# tes1.net
KiCad netlist of a schematic drawn in EAGLE
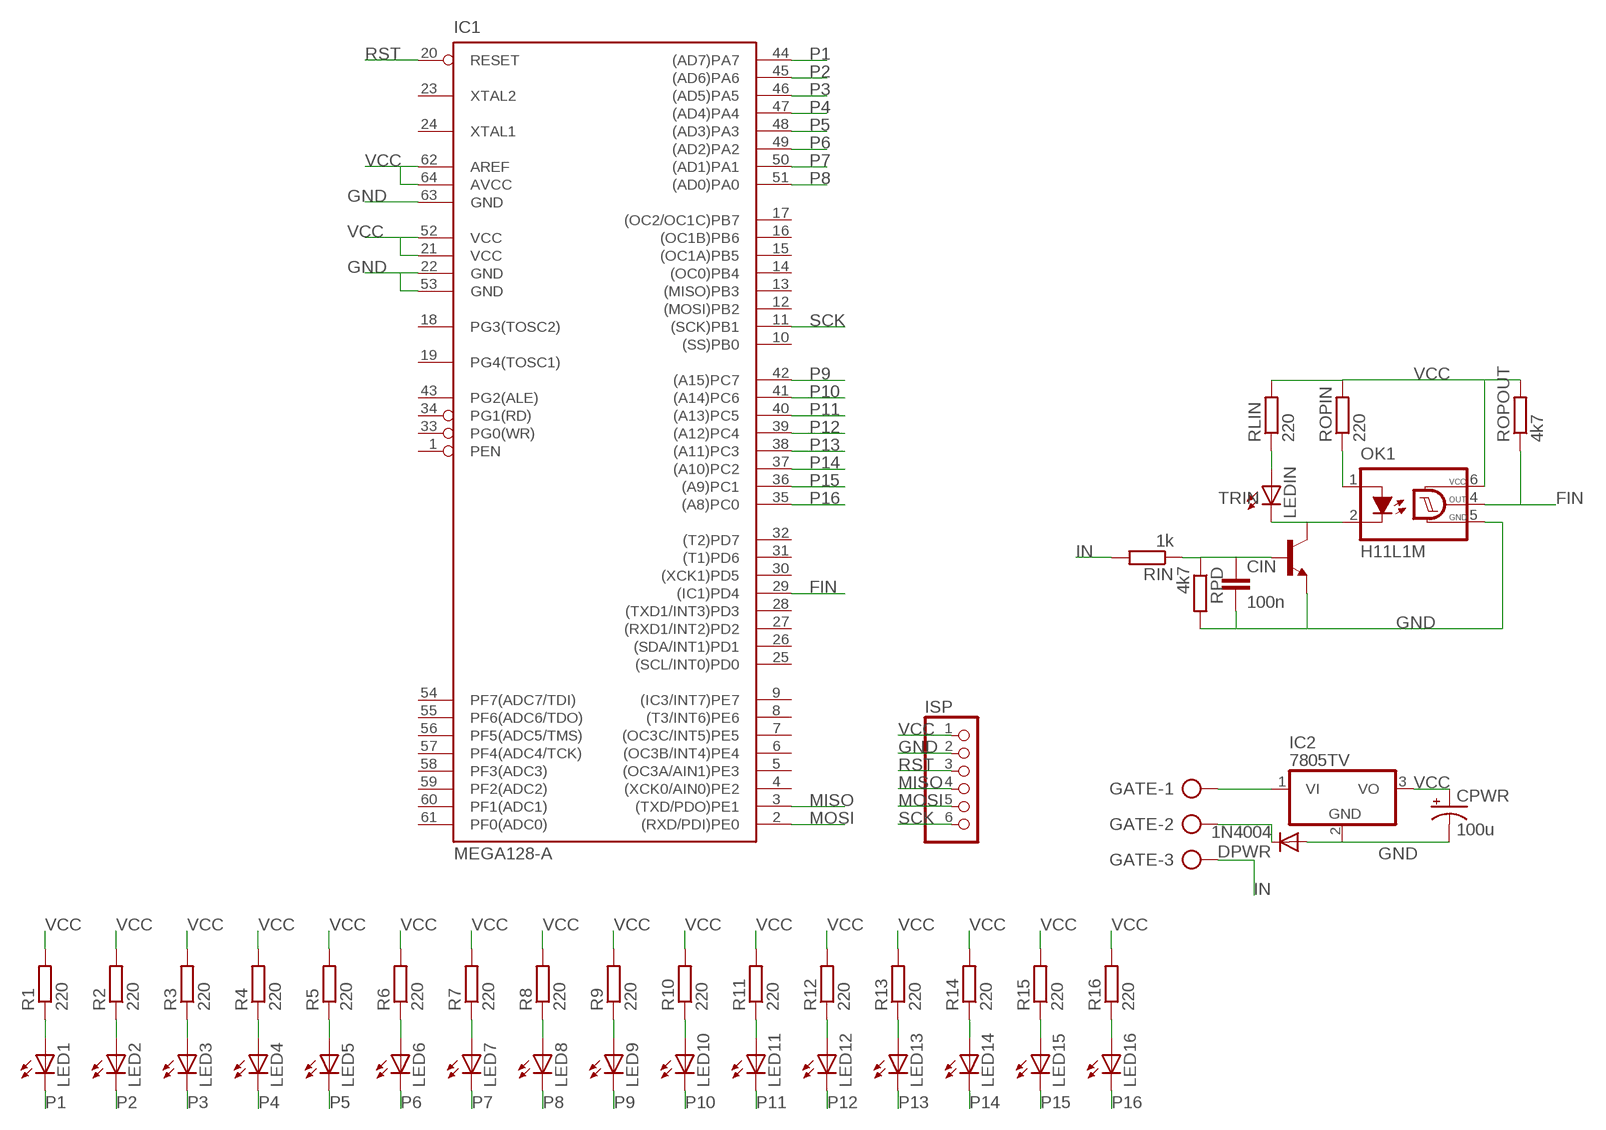
[diagram p0: schematic, sheet 1]

(export (version "E")
  (design (tool "Eeschema 10.0.6"))
  (components
    (comp (ref "CIN")
      (value "100n")
      (footprint "eagle-import:C050-024X044")
      (libsource (lib "eagle-import") (part "C-EU050-024X044"))
    )
    (comp (ref "CPWR")
      (value "100u")
      (footprint "eagle-import:E2-5")
      (libsource (lib "eagle-import") (part "CPOL-USE2-5"))
    )
    (comp (ref "DPWR")
      (value "1N4004")
      (footprint "eagle-import:DO41-10")
      (libsource (lib "eagle-import") (part "1N4004"))
    )
    (comp (ref "GATE")
      (value "AK300/3")
      (footprint "eagle-import:AK300_3")
      (libsource (lib "eagle-import") (part "AK300/3"))
    )
    (comp (ref "IC1")
      (value "MEGA128-A")
      (footprint "eagle-import:TQFP64")
      (fields (field (name "MPN") "ATMEGA128-16AU"))
      (libsource (lib "eagle-import") (part "MEGA128-A"))
    )
    (comp (ref "IC2")
      (value "7805TV")
      (footprint "eagle-import:TO220V")
      (libsource (lib "eagle-import") (part "78TV05"))
    )
    (comp (ref "ISP")
      (value "PINHD-1X6")
      (footprint "eagle-import:1X06")
      (libsource (lib "eagle-import") (part "PINHD-1X6"))
    )
    (comp (ref "LED1")
      (value "LED3MM")
      (footprint "eagle-import:LED3MM")
      (libsource (lib "eagle-import") (part "LED3MM"))
    )
    (comp (ref "LED2")
      (value "LED3MM")
      (footprint "eagle-import:LED3MM")
      (libsource (lib "eagle-import") (part "LED3MM"))
    )
    (comp (ref "LED3")
      (value "LED3MM")
      (footprint "eagle-import:LED3MM")
      (libsource (lib "eagle-import") (part "LED3MM"))
    )
    (comp (ref "LED4")
      (value "LED3MM")
      (footprint "eagle-import:LED3MM")
      (libsource (lib "eagle-import") (part "LED3MM"))
    )
    (comp (ref "LED5")
      (value "LED3MM")
      (footprint "eagle-import:LED3MM")
      (libsource (lib "eagle-import") (part "LED3MM"))
    )
    (comp (ref "LED6")
      (value "LED3MM")
      (footprint "eagle-import:LED3MM")
      (libsource (lib "eagle-import") (part "LED3MM"))
    )
    (comp (ref "LED7")
      (value "LED3MM")
      (footprint "eagle-import:LED3MM")
      (libsource (lib "eagle-import") (part "LED3MM"))
    )
    (comp (ref "LED8")
      (value "LED3MM")
      (footprint "eagle-import:LED3MM")
      (libsource (lib "eagle-import") (part "LED3MM"))
    )
    (comp (ref "LED9")
      (value "LED3MM")
      (footprint "eagle-import:LED3MM")
      (libsource (lib "eagle-import") (part "LED3MM"))
    )
    (comp (ref "LED10")
      (value "LED3MM")
      (footprint "eagle-import:LED3MM")
      (libsource (lib "eagle-import") (part "LED3MM"))
    )
    (comp (ref "LED11")
      (value "LED3MM")
      (footprint "eagle-import:LED3MM")
      (libsource (lib "eagle-import") (part "LED3MM"))
    )
    (comp (ref "LED12")
      (value "LED3MM")
      (footprint "eagle-import:LED3MM")
      (libsource (lib "eagle-import") (part "LED3MM"))
    )
    (comp (ref "LED13")
      (value "LED3MM")
      (footprint "eagle-import:LED3MM")
      (libsource (lib "eagle-import") (part "LED3MM"))
    )
    (comp (ref "LED14")
      (value "LED3MM")
      (footprint "eagle-import:LED3MM")
      (libsource (lib "eagle-import") (part "LED3MM"))
    )
    (comp (ref "LED15")
      (value "LED3MM")
      (footprint "eagle-import:LED3MM")
      (libsource (lib "eagle-import") (part "LED3MM"))
    )
    (comp (ref "LED16")
      (value "LED3MM")
      (footprint "eagle-import:LED3MM")
      (libsource (lib "eagle-import") (part "LED3MM"))
    )
    (comp (ref "LEDIN")
      (value "LED3MM")
      (footprint "eagle-import:LED3MM")
      (libsource (lib "eagle-import") (part "LED3MM"))
    )
    (comp (ref "OK1")
      (value "H11L1M")
      (footprint "eagle-import:DIL06")
      (fields (field (name "MF") "FAIRCHILD SEMICONDUCTOR") (field (name "MPN") "H11L1-M"))
      (libsource (lib "eagle-import") (part "H11LM1"))
    )
    (comp (ref "R1")
      (value "220")
      (footprint "eagle-import:0204_7")
      (libsource (lib "eagle-import") (part "R-EU_0204/7"))
    )
    (comp (ref "R2")
      (value "220")
      (footprint "eagle-import:0204_7")
      (libsource (lib "eagle-import") (part "R-EU_0204/7"))
    )
    (comp (ref "R3")
      (value "220")
      (footprint "eagle-import:0204_7")
      (libsource (lib "eagle-import") (part "R-EU_0204/7"))
    )
    (comp (ref "R4")
      (value "220")
      (footprint "eagle-import:0204_7")
      (libsource (lib "eagle-import") (part "R-EU_0204/7"))
    )
    (comp (ref "R5")
      (value "220")
      (footprint "eagle-import:0204_7")
      (libsource (lib "eagle-import") (part "R-EU_0204/7"))
    )
    (comp (ref "R6")
      (value "220")
      (footprint "eagle-import:0204_7")
      (libsource (lib "eagle-import") (part "R-EU_0204/7"))
    )
    (comp (ref "R7")
      (value "220")
      (footprint "eagle-import:0204_7")
      (libsource (lib "eagle-import") (part "R-EU_0204/7"))
    )
    (comp (ref "R8")
      (value "220")
      (footprint "eagle-import:0204_7")
      (libsource (lib "eagle-import") (part "R-EU_0204/7"))
    )
    (comp (ref "R9")
      (value "220")
      (footprint "eagle-import:0204_7")
      (libsource (lib "eagle-import") (part "R-EU_0204/7"))
    )
    (comp (ref "R10")
      (value "220")
      (footprint "eagle-import:0204_7")
      (libsource (lib "eagle-import") (part "R-EU_0204/7"))
    )
    (comp (ref "R11")
      (value "220")
      (footprint "eagle-import:0204_7")
      (libsource (lib "eagle-import") (part "R-EU_0204/7"))
    )
    (comp (ref "R12")
      (value "220")
      (footprint "eagle-import:0204_7")
      (libsource (lib "eagle-import") (part "R-EU_0204/7"))
    )
    (comp (ref "R13")
      (value "220")
      (footprint "eagle-import:0204_7")
      (libsource (lib "eagle-import") (part "R-EU_0204/7"))
    )
    (comp (ref "R14")
      (value "220")
      (footprint "eagle-import:0204_7")
      (libsource (lib "eagle-import") (part "R-EU_0204/7"))
    )
    (comp (ref "R15")
      (value "220")
      (footprint "eagle-import:0204_7")
      (libsource (lib "eagle-import") (part "R-EU_0204/7"))
    )
    (comp (ref "R16")
      (value "220")
      (footprint "eagle-import:0204_7")
      (libsource (lib "eagle-import") (part "R-EU_0204/7"))
    )
    (comp (ref "RIN")
      (value "1k")
      (footprint "eagle-import:0204_7")
      (libsource (lib "eagle-import") (part "R-EU_0204/7"))
    )
    (comp (ref "RLIN")
      (value "220")
      (footprint "eagle-import:0204_7")
      (libsource (lib "eagle-import") (part "R-EU_0204/7"))
    )
    (comp (ref "ROPIN")
      (value "220")
      (footprint "eagle-import:0204_7")
      (libsource (lib "eagle-import") (part "R-EU_0204/7"))
    )
    (comp (ref "ROPOUT")
      (value "4k7")
      (footprint "eagle-import:0204_7")
      (libsource (lib "eagle-import") (part "R-EU_0204/7"))
    )
    (comp (ref "RPD")
      (value "4k7")
      (footprint "eagle-import:0204_7")
      (libsource (lib "eagle-import") (part "R-EU_0204/7"))
    )
    (comp (ref "TRIN")
      (value "-NPN-TO92-EBC")
      (footprint "eagle-import:TO92-EBC")
      (libsource (lib "eagle-import") (part "-NPN-TO92-EBC"))
    )
  )
  (nets
    (net (code "1") (name "/FIN") (class "Default")
      (node (ref "IC1") (pin "29") (pinfunction "(IC1)PD4_29") (pintype "bidirectional"))
      (node (ref "OK1") (pin "4") (pinfunction "OUT_4") (pintype "output"))
      (node (ref "ROPOUT") (pin "1") (pinfunction "1_1") (pintype "passive"))
    )
    (net (code "2") (name "/GND") (class "Default")
      (node (ref "CIN") (pin "2") (pinfunction "2_2") (pintype "passive"))
      (node (ref "CPWR") (pin "-") (pinfunction "-_-") (pintype "passive"))
      (node (ref "DPWR") (pin "A") (pinfunction "A_A") (pintype "passive"))
      (node (ref "IC1") (pin "22") (pinfunction "GND_22") (pintype "power_in"))
      (node (ref "IC1") (pin "53") (pinfunction "GND_53") (pintype "power_in"))
      (node (ref "IC1") (pin "63") (pinfunction "GND_63") (pintype "power_in"))
      (node (ref "IC2") (pin "2") (pinfunction "GND_2") (pintype "passive"))
      (node (ref "ISP") (pin "2") (pinfunction "2_2") (pintype "passive"))
      (node (ref "OK1") (pin "5") (pinfunction "GND_5") (pintype "power_in"))
      (node (ref "RPD") (pin "2") (pinfunction "2_2") (pintype "passive"))
      (node (ref "TRIN") (pin "E") (pinfunction "E_E") (pintype "passive"))
    )
    (net (code "3") (name "/IN") (class "Default")
      (node (ref "GATE") (pin "3") (pinfunction "KL_3") (pintype "passive"))
      (node (ref "RIN") (pin "2") (pinfunction "2_2") (pintype "passive"))
    )
    (net (code "4") (name "/MISO") (class "Default")
      (node (ref "IC1") (pin "3") (pinfunction "(TXD/PDO)PE1_3") (pintype "bidirectional"))
      (node (ref "ISP") (pin "4") (pinfunction "4_4") (pintype "passive"))
    )
    (net (code "5") (name "/MOSI") (class "Default")
      (node (ref "IC1") (pin "2") (pinfunction "(RXD/PDI)PE0_2") (pintype "bidirectional"))
      (node (ref "ISP") (pin "5") (pinfunction "5_5") (pintype "passive"))
    )
    (net (code "6") (name "/P1") (class "Default")
      (node (ref "IC1") (pin "44") (pinfunction "(AD7)PA7_44") (pintype "bidirectional"))
      (node (ref "LED1") (pin "K") (pinfunction "C_K") (pintype "passive"))
    )
    (net (code "7") (name "/P2") (class "Default")
      (node (ref "IC1") (pin "45") (pinfunction "(AD6)PA6_45") (pintype "bidirectional"))
      (node (ref "LED2") (pin "K") (pinfunction "C_K") (pintype "passive"))
    )
    (net (code "8") (name "/P3") (class "Default")
      (node (ref "IC1") (pin "46") (pinfunction "(AD5)PA5_46") (pintype "bidirectional"))
      (node (ref "LED3") (pin "K") (pinfunction "C_K") (pintype "passive"))
    )
    (net (code "9") (name "/P4") (class "Default")
      (node (ref "IC1") (pin "47") (pinfunction "(AD4)PA4_47") (pintype "bidirectional"))
      (node (ref "LED4") (pin "K") (pinfunction "C_K") (pintype "passive"))
    )
    (net (code "10") (name "/P5") (class "Default")
      (node (ref "IC1") (pin "48") (pinfunction "(AD3)PA3_48") (pintype "bidirectional"))
      (node (ref "LED5") (pin "K") (pinfunction "C_K") (pintype "passive"))
    )
    (net (code "11") (name "/P6") (class "Default")
      (node (ref "IC1") (pin "49") (pinfunction "(AD2)PA2_49") (pintype "bidirectional"))
      (node (ref "LED6") (pin "K") (pinfunction "C_K") (pintype "passive"))
    )
    (net (code "12") (name "/P7") (class "Default")
      (node (ref "IC1") (pin "50") (pinfunction "(AD1)PA1_50") (pintype "bidirectional"))
      (node (ref "LED7") (pin "K") (pinfunction "C_K") (pintype "passive"))
    )
    (net (code "13") (name "/P8") (class "Default")
      (node (ref "IC1") (pin "51") (pinfunction "(AD0)PA0_51") (pintype "bidirectional"))
      (node (ref "LED8") (pin "K") (pinfunction "C_K") (pintype "passive"))
    )
    (net (code "14") (name "/P9") (class "Default")
      (node (ref "IC1") (pin "42") (pinfunction "(A15)PC7_42") (pintype "output"))
      (node (ref "LED9") (pin "K") (pinfunction "C_K") (pintype "passive"))
    )
    (net (code "15") (name "/P10") (class "Default")
      (node (ref "IC1") (pin "41") (pinfunction "(A14)PC6_41") (pintype "output"))
      (node (ref "LED10") (pin "K") (pinfunction "C_K") (pintype "passive"))
    )
    (net (code "16") (name "/P11") (class "Default")
      (node (ref "IC1") (pin "40") (pinfunction "(A13)PC5_40") (pintype "output"))
      (node (ref "LED11") (pin "K") (pinfunction "C_K") (pintype "passive"))
    )
    (net (code "17") (name "/P12") (class "Default")
      (node (ref "IC1") (pin "39") (pinfunction "(A12)PC4_39") (pintype "output"))
      (node (ref "LED12") (pin "K") (pinfunction "C_K") (pintype "passive"))
    )
    (net (code "18") (name "/P13") (class "Default")
      (node (ref "IC1") (pin "38") (pinfunction "(A11)PC3_38") (pintype "output"))
      (node (ref "LED13") (pin "K") (pinfunction "C_K") (pintype "passive"))
    )
    (net (code "19") (name "/P14") (class "Default")
      (node (ref "IC1") (pin "37") (pinfunction "(A10)PC2_37") (pintype "output"))
      (node (ref "LED14") (pin "K") (pinfunction "C_K") (pintype "passive"))
    )
    (net (code "20") (name "/P15") (class "Default")
      (node (ref "IC1") (pin "36") (pinfunction "(A9)PC1_36") (pintype "output"))
      (node (ref "LED15") (pin "K") (pinfunction "C_K") (pintype "passive"))
    )
    (net (code "21") (name "/P16") (class "Default")
      (node (ref "IC1") (pin "35") (pinfunction "(A8)PC0_35") (pintype "output"))
      (node (ref "LED16") (pin "K") (pinfunction "C_K") (pintype "passive"))
    )
    (net (code "22") (name "/RST") (class "Default")
      (node (ref "IC1") (pin "20") (pinfunction "RESET_20") (pintype "input"))
      (node (ref "ISP") (pin "3") (pinfunction "3_3") (pintype "passive"))
    )
    (net (code "23") (name "/SCK") (class "Default")
      (node (ref "IC1") (pin "11") (pinfunction "(SCK)PB1_11") (pintype "bidirectional"))
      (node (ref "ISP") (pin "6") (pinfunction "6_6") (pintype "passive"))
    )
    (net (code "24") (name "/VCC") (class "Default")
      (node (ref "CPWR") (pin "+") (pinfunction "+_+") (pintype "passive"))
      (node (ref "IC1") (pin "21") (pinfunction "VCC_21") (pintype "power_in"))
      (node (ref "IC1") (pin "52") (pinfunction "VCC_52") (pintype "power_in"))
      (node (ref "IC1") (pin "62") (pinfunction "AREF_62") (pintype "passive"))
      (node (ref "IC1") (pin "64") (pinfunction "AVCC_64") (pintype "power_in"))
      (node (ref "IC2") (pin "3") (pinfunction "VO_3") (pintype "passive"))
      (node (ref "ISP") (pin "1") (pinfunction "1_1") (pintype "passive"))
      (node (ref "OK1") (pin "6") (pinfunction "VCC_6") (pintype "power_in"))
      (node (ref "R1") (pin "2") (pinfunction "2_2") (pintype "passive"))
      (node (ref "R10") (pin "2") (pinfunction "2_2") (pintype "passive"))
      (node (ref "R11") (pin "2") (pinfunction "2_2") (pintype "passive"))
      (node (ref "R12") (pin "2") (pinfunction "2_2") (pintype "passive"))
      (node (ref "R13") (pin "2") (pinfunction "2_2") (pintype "passive"))
      (node (ref "R14") (pin "2") (pinfunction "2_2") (pintype "passive"))
      (node (ref "R15") (pin "2") (pinfunction "2_2") (pintype "passive"))
      (node (ref "R16") (pin "2") (pinfunction "2_2") (pintype "passive"))
      (node (ref "R2") (pin "2") (pinfunction "2_2") (pintype "passive"))
      (node (ref "R3") (pin "2") (pinfunction "2_2") (pintype "passive"))
      (node (ref "R4") (pin "2") (pinfunction "2_2") (pintype "passive"))
      (node (ref "R5") (pin "2") (pinfunction "2_2") (pintype "passive"))
      (node (ref "R6") (pin "2") (pinfunction "2_2") (pintype "passive"))
      (node (ref "R7") (pin "2") (pinfunction "2_2") (pintype "passive"))
      (node (ref "R8") (pin "2") (pinfunction "2_2") (pintype "passive"))
      (node (ref "R9") (pin "2") (pinfunction "2_2") (pintype "passive"))
      (node (ref "RLIN") (pin "2") (pinfunction "2_2") (pintype "passive"))
      (node (ref "ROPIN") (pin "2") (pinfunction "2_2") (pintype "passive"))
      (node (ref "ROPOUT") (pin "2") (pinfunction "2_2") (pintype "passive"))
    )
    (net (code "25") (name "Net-(CIN-Pad1)") (class "Default")
      (node (ref "CIN") (pin "1") (pinfunction "1_1") (pintype "passive"))
      (node (ref "RIN") (pin "1") (pinfunction "1_1") (pintype "passive"))
      (node (ref "RPD") (pin "1") (pinfunction "1_1") (pintype "passive"))
      (node (ref "TRIN") (pin "B") (pinfunction "B_B") (pintype "passive"))
    )
    (net (code "26") (name "Net-(GATEA-KL)") (class "Default")
      (node (ref "GATE") (pin "1") (pinfunction "KL_1") (pintype "passive"))
      (node (ref "IC2") (pin "1") (pinfunction "VI_1") (pintype "input"))
    )
    (net (code "27") (name "Net-(GATEB-KL)") (class "Default")
      (node (ref "DPWR") (pin "C") (pinfunction "C_C") (pintype "passive"))
      (node (ref "GATE") (pin "2") (pinfunction "KL_2") (pintype "passive"))
    )
    (net (code "28") (name "Net-(LED1-PadA)") (class "Default")
      (node (ref "LED1") (pin "A") (pinfunction "A_A") (pintype "passive"))
      (node (ref "R1") (pin "1") (pinfunction "1_1") (pintype "passive"))
    )
    (net (code "29") (name "Net-(LED2-PadA)") (class "Default")
      (node (ref "LED2") (pin "A") (pinfunction "A_A") (pintype "passive"))
      (node (ref "R2") (pin "1") (pinfunction "1_1") (pintype "passive"))
    )
    (net (code "30") (name "Net-(LED3-PadA)") (class "Default")
      (node (ref "LED3") (pin "A") (pinfunction "A_A") (pintype "passive"))
      (node (ref "R3") (pin "1") (pinfunction "1_1") (pintype "passive"))
    )
    (net (code "31") (name "Net-(LED4-PadA)") (class "Default")
      (node (ref "LED4") (pin "A") (pinfunction "A_A") (pintype "passive"))
      (node (ref "R4") (pin "1") (pinfunction "1_1") (pintype "passive"))
    )
    (net (code "32") (name "Net-(LED5-PadA)") (class "Default")
      (node (ref "LED5") (pin "A") (pinfunction "A_A") (pintype "passive"))
      (node (ref "R5") (pin "1") (pinfunction "1_1") (pintype "passive"))
    )
    (net (code "33") (name "Net-(LED6-PadA)") (class "Default")
      (node (ref "LED6") (pin "A") (pinfunction "A_A") (pintype "passive"))
      (node (ref "R6") (pin "1") (pinfunction "1_1") (pintype "passive"))
    )
    (net (code "34") (name "Net-(LED7-PadA)") (class "Default")
      (node (ref "LED7") (pin "A") (pinfunction "A_A") (pintype "passive"))
      (node (ref "R7") (pin "1") (pinfunction "1_1") (pintype "passive"))
    )
    (net (code "35") (name "Net-(LED8-PadA)") (class "Default")
      (node (ref "LED8") (pin "A") (pinfunction "A_A") (pintype "passive"))
      (node (ref "R8") (pin "1") (pinfunction "1_1") (pintype "passive"))
    )
    (net (code "36") (name "Net-(LED9-PadA)") (class "Default")
      (node (ref "LED9") (pin "A") (pinfunction "A_A") (pintype "passive"))
      (node (ref "R9") (pin "1") (pinfunction "1_1") (pintype "passive"))
    )
    (net (code "37") (name "Net-(LED10-PadA)") (class "Default")
      (node (ref "LED10") (pin "A") (pinfunction "A_A") (pintype "passive"))
      (node (ref "R10") (pin "1") (pinfunction "1_1") (pintype "passive"))
    )
    (net (code "38") (name "Net-(LED11-PadA)") (class "Default")
      (node (ref "LED11") (pin "A") (pinfunction "A_A") (pintype "passive"))
      (node (ref "R11") (pin "1") (pinfunction "1_1") (pintype "passive"))
    )
    (net (code "39") (name "Net-(LED12-PadA)") (class "Default")
      (node (ref "LED12") (pin "A") (pinfunction "A_A") (pintype "passive"))
      (node (ref "R12") (pin "1") (pinfunction "1_1") (pintype "passive"))
    )
    (net (code "40") (name "Net-(LED13-PadA)") (class "Default")
      (node (ref "LED13") (pin "A") (pinfunction "A_A") (pintype "passive"))
      (node (ref "R13") (pin "1") (pinfunction "1_1") (pintype "passive"))
    )
    (net (code "41") (name "Net-(LED14-PadA)") (class "Default")
      (node (ref "LED14") (pin "A") (pinfunction "A_A") (pintype "passive"))
      (node (ref "R14") (pin "1") (pinfunction "1_1") (pintype "passive"))
    )
    (net (code "42") (name "Net-(LED15-PadA)") (class "Default")
      (node (ref "LED15") (pin "A") (pinfunction "A_A") (pintype "passive"))
      (node (ref "R15") (pin "1") (pinfunction "1_1") (pintype "passive"))
    )
    (net (code "43") (name "Net-(LED16-PadA)") (class "Default")
      (node (ref "LED16") (pin "A") (pinfunction "A_A") (pintype "passive"))
      (node (ref "R16") (pin "1") (pinfunction "1_1") (pintype "passive"))
    )
    (net (code "44") (name "Net-(LEDIN-C)") (class "Default")
      (node (ref "LEDIN") (pin "K") (pinfunction "C_K") (pintype "passive"))
      (node (ref "OK1") (pin "2") (pinfunction "C_2") (pintype "passive"))
      (node (ref "TRIN") (pin "C") (pinfunction "C_C") (pintype "passive"))
    )
    (net (code "45") (name "Net-(LEDIN-PadA)") (class "Default")
      (node (ref "LEDIN") (pin "A") (pinfunction "A_A") (pintype "passive"))
      (node (ref "RLIN") (pin "1") (pinfunction "1_1") (pintype "passive"))
    )
    (net (code "46") (name "Net-(OK1-A)") (class "Default")
      (node (ref "OK1") (pin "1") (pinfunction "A_1") (pintype "passive"))
      (node (ref "ROPIN") (pin "1") (pinfunction "1_1") (pintype "passive"))
    )
    (net (code "47") (name "unconnected-(IC1-(IC3{slash}INT7)PE7-Pad9)") (class "Default")
      (node (ref "IC1") (pin "9") (pinfunction "(IC3/INT7)PE7_9") (pintype "bidirectional"))
    )
    (net (code "48") (name "unconnected-(IC1-(MISO)PB3-Pad13)") (class "Default")
      (node (ref "IC1") (pin "13") (pinfunction "(MISO)PB3_13") (pintype "bidirectional"))
    )
    (net (code "49") (name "unconnected-(IC1-(MOSI)PB2-Pad12)") (class "Default")
      (node (ref "IC1") (pin "12") (pinfunction "(MOSI)PB2_12") (pintype "bidirectional"))
    )
    (net (code "50") (name "unconnected-(IC1-(OC0)PB4-Pad14)") (class "Default")
      (node (ref "IC1") (pin "14") (pinfunction "(OC0)PB4_14") (pintype "bidirectional"))
    )
    (net (code "51") (name "unconnected-(IC1-(OC1A)PB5-Pad15)") (class "Default")
      (node (ref "IC1") (pin "15") (pinfunction "(OC1A)PB5_15") (pintype "bidirectional"))
    )
    (net (code "52") (name "unconnected-(IC1-(OC1B)PB6-Pad16)") (class "Default")
      (node (ref "IC1") (pin "16") (pinfunction "(OC1B)PB6_16") (pintype "bidirectional"))
    )
    (net (code "53") (name "unconnected-(IC1-(OC2{slash}OC1C)PB7-Pad17)") (class "Default")
      (node (ref "IC1") (pin "17") (pinfunction "(OC2/OC1C)PB7_17") (pintype "bidirectional"))
    )
    (net (code "54") (name "unconnected-(IC1-(OC3A{slash}AIN1)PE3-Pad5)") (class "Default")
      (node (ref "IC1") (pin "5") (pinfunction "(OC3A/AIN1)PE3_5") (pintype "bidirectional"))
    )
    (net (code "55") (name "unconnected-(IC1-(OC3B{slash}INT4)PE4-Pad6)") (class "Default")
      (node (ref "IC1") (pin "6") (pinfunction "(OC3B/INT4)PE4_6") (pintype "bidirectional"))
    )
    (net (code "56") (name "unconnected-(IC1-(OC3C{slash}INT5)PE5-Pad7)") (class "Default")
      (node (ref "IC1") (pin "7") (pinfunction "(OC3C/INT5)PE5_7") (pintype "bidirectional"))
    )
    (net (code "57") (name "unconnected-(IC1-(RXD1{slash}INT2)PD2-Pad27)") (class "Default")
      (node (ref "IC1") (pin "27") (pinfunction "(RXD1/INT2)PD2_27") (pintype "bidirectional"))
    )
    (net (code "58") (name "unconnected-(IC1-(SCL{slash}INT0)PD0-Pad25)") (class "Default")
      (node (ref "IC1") (pin "25") (pinfunction "(SCL/INT0)PD0_25") (pintype "bidirectional"))
    )
    (net (code "59") (name "unconnected-(IC1-(SDA{slash}INT1)PD1-Pad26)") (class "Default")
      (node (ref "IC1") (pin "26") (pinfunction "(SDA/INT1)PD1_26") (pintype "bidirectional"))
    )
    (net (code "60") (name "unconnected-(IC1-(SS)PB0-Pad10)") (class "Default")
      (node (ref "IC1") (pin "10") (pinfunction "(SS)PB0_10") (pintype "bidirectional"))
    )
    (net (code "61") (name "unconnected-(IC1-(T1)PD6-Pad31)") (class "Default")
      (node (ref "IC1") (pin "31") (pinfunction "(T1)PD6_31") (pintype "bidirectional"))
    )
    (net (code "62") (name "unconnected-(IC1-(T2)PD7-Pad32)") (class "Default")
      (node (ref "IC1") (pin "32") (pinfunction "(T2)PD7_32") (pintype "bidirectional"))
    )
    (net (code "63") (name "unconnected-(IC1-(T3{slash}INT6)PE6-Pad8)") (class "Default")
      (node (ref "IC1") (pin "8") (pinfunction "(T3/INT6)PE6_8") (pintype "bidirectional"))
    )
    (net (code "64") (name "unconnected-(IC1-(TXD1{slash}INT3)PD3-Pad28)") (class "Default")
      (node (ref "IC1") (pin "28") (pinfunction "(TXD1/INT3)PD3_28") (pintype "bidirectional"))
    )
    (net (code "65") (name "unconnected-(IC1-(XCK0{slash}AIN0)PE2-Pad4)") (class "Default")
      (node (ref "IC1") (pin "4") (pinfunction "(XCK0/AIN0)PE2_4") (pintype "bidirectional"))
    )
    (net (code "66") (name "unconnected-(IC1-(XCK1)PD5-Pad30)") (class "Default")
      (node (ref "IC1") (pin "30") (pinfunction "(XCK1)PD5_30") (pintype "bidirectional"))
    )
    (net (code "67") (name "unconnected-(IC1-PEN-Pad1)") (class "Default")
      (node (ref "IC1") (pin "1") (pinfunction "PEN_1") (pintype "input"))
    )
    (net (code "68") (name "unconnected-(IC1-PF0(ADC0)-Pad61)") (class "Default")
      (node (ref "IC1") (pin "61") (pinfunction "PF0(ADC0)_61") (pintype "input"))
    )
    (net (code "69") (name "unconnected-(IC1-PF1(ADC1)-Pad60)") (class "Default")
      (node (ref "IC1") (pin "60") (pinfunction "PF1(ADC1)_60") (pintype "input"))
    )
    (net (code "70") (name "unconnected-(IC1-PF2(ADC2)-Pad59)") (class "Default")
      (node (ref "IC1") (pin "59") (pinfunction "PF2(ADC2)_59") (pintype "input"))
    )
    (net (code "71") (name "unconnected-(IC1-PF3(ADC3)-Pad58)") (class "Default")
      (node (ref "IC1") (pin "58") (pinfunction "PF3(ADC3)_58") (pintype "input"))
    )
    (net (code "72") (name "unconnected-(IC1-PF4(ADC4{slash}TCK)-Pad57)") (class "Default")
      (node (ref "IC1") (pin "57") (pinfunction "PF4(ADC4/TCK)_57") (pintype "input"))
    )
    (net (code "73") (name "unconnected-(IC1-PF5(ADC5{slash}TMS)-Pad56)") (class "Default")
      (node (ref "IC1") (pin "56") (pinfunction "PF5(ADC5/TMS)_56") (pintype "input"))
    )
    (net (code "74") (name "unconnected-(IC1-PF6(ADC6{slash}TDO)-Pad55)") (class "Default")
      (node (ref "IC1") (pin "55") (pinfunction "PF6(ADC6/TDO)_55") (pintype "input"))
    )
    (net (code "75") (name "unconnected-(IC1-PF7(ADC7{slash}TDI)-Pad54)") (class "Default")
      (node (ref "IC1") (pin "54") (pinfunction "PF7(ADC7/TDI)_54") (pintype "input"))
    )
    (net (code "76") (name "unconnected-(IC1-PG0(WR)-Pad33)") (class "Default")
      (node (ref "IC1") (pin "33") (pinfunction "PG0(WR)_33") (pintype "bidirectional"))
    )
    (net (code "77") (name "unconnected-(IC1-PG1(RD)-Pad34)") (class "Default")
      (node (ref "IC1") (pin "34") (pinfunction "PG1(RD)_34") (pintype "bidirectional"))
    )
    (net (code "78") (name "unconnected-(IC1-PG2(ALE)-Pad43)") (class "Default")
      (node (ref "IC1") (pin "43") (pinfunction "PG2(ALE)_43") (pintype "bidirectional"))
    )
    (net (code "79") (name "unconnected-(IC1-PG3(TOSC2)-Pad18)") (class "Default")
      (node (ref "IC1") (pin "18") (pinfunction "PG3(TOSC2)_18") (pintype "bidirectional"))
    )
    (net (code "80") (name "unconnected-(IC1-PG4(TOSC1)-Pad19)") (class "Default")
      (node (ref "IC1") (pin "19") (pinfunction "PG4(TOSC1)_19") (pintype "bidirectional"))
    )
    (net (code "81") (name "unconnected-(IC1-XTAL1-Pad24)") (class "Default")
      (node (ref "IC1") (pin "24") (pinfunction "XTAL1_24") (pintype "bidirectional"))
    )
    (net (code "82") (name "unconnected-(IC1-XTAL2-Pad23)") (class "Default")
      (node (ref "IC1") (pin "23") (pinfunction "XTAL2_23") (pintype "bidirectional"))
    )
  )
)
